# Altium_LED-Resistor.net
KiCad netlist of a schematic drawn in Altium Designer
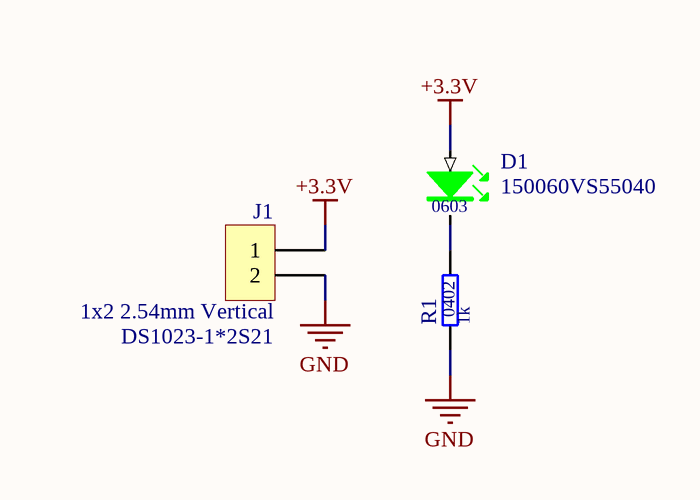
[diagram p0: Altium_LED-Resistor.SchDoc]

(export (version "E")
  (design (tool "Eeschema 10.0.6"))
  (components
    (comp (ref "D1")
      (value "150060VS55040")
      (footprint "OL_0603_1608")
      (description "LED GREEN")
      (fields
        (field (name "SCH_FOOTPRINT") "0603")
        (field (name "PART NUMBER") "OL_G_0603_150060VS55040")
        (field (name "MANUFACTURER") "Wurth")
      )
      (libsource (lib "Library") (part "OL_G"))
    )
    (comp (ref "J1")
      (value "DS1023-1*2S21")
      (footprint "J_HEADER_1x2_2.54_VERTICAL")
      (description "Pin Header")
      (fields
        (field (name "SCH_FOOTPRINT") "1x2 2.54mm Vertical")
        (field (name "PART NUMBER") "J_HEADER_1x2_2.54_VERTICAL")
        (field (name "MANUFACTURER") "Connfly")
      )
      (libsource (lib "Library") (part "J_HEADER_1x2"))
    )
    (comp (ref "R1")
      (value "1k")
      (footprint "R_0402_1005")
      (fields
        (field (name "SCH_FOOTPRINT") "0402")
        (field (name "PART NUMBER") "R_1k_0402_1")
        (field (name "VOLTAGE") "50V")
        (field (name "POWER") "63mW")
      )
      (libsource (lib "Library") (part "R"))
    )
  )
  (nets
    (net (code "1") (name "+3.3V") (class "Default")
      (node (ref "D1") (pin "2") (pinfunction "A_2") (pintype "input"))
      (node (ref "J1") (pin "1") (pinfunction "1_1") (pintype "passive"))
    )
    (net (code "2") (name "GND") (class "Default")
      (node (ref "J1") (pin "2") (pinfunction "2_2") (pintype "passive"))
      (node (ref "R1") (pin "1") (pinfunction "1_1") (pintype "passive"))
    )
    (net (code "3") (name "Net-(D1-K)") (class "Default")
      (node (ref "D1") (pin "1") (pinfunction "K_1") (pintype "output"))
      (node (ref "R1") (pin "2") (pinfunction "2_2") (pintype "passive"))
    )
  )
)
